# STM32-PROX_7.net
KiCad netlist of a schematic drawn in Altium Designer
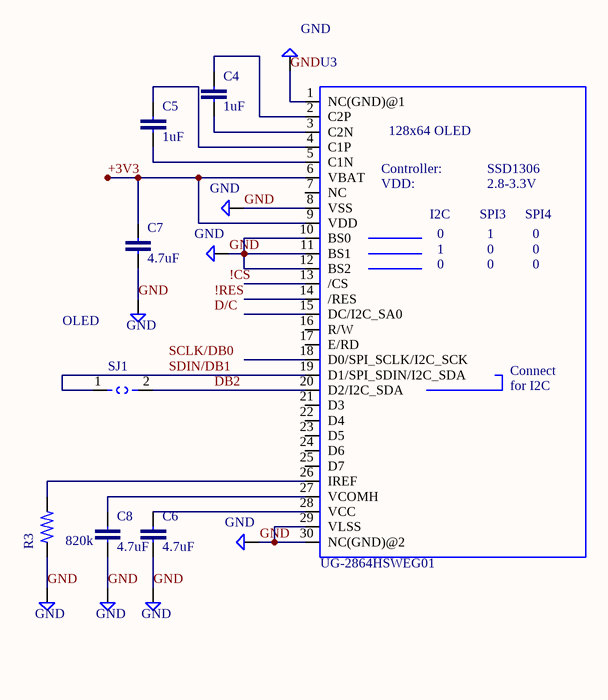
[diagram p0: STM32-PROX_7.SchDoc]

(export (version "E")
  (design (tool "Eeschema 10.0.6"))
  (components
    (comp (ref "C4") (value "1uF") (footprint "0805") (libsource (lib "STM32-PROX") (part "CAP0805")))
    (comp (ref "C5") (value "1uF") (footprint "0805") (libsource (lib "STM32-PROX") (part "CAP0805")))
    (comp (ref "C6") (value "4.7uF") (footprint "0805") (libsource (lib "STM32-PROX") (part "CAP0805")))
    (comp (ref "C7") (value "4.7uF") (footprint "0805") (libsource (lib "STM32-PROX") (part "CAP0805")))
    (comp (ref "C8") (value "4.7uF") (footprint "0805") (libsource (lib "STM32-PROX") (part "CAP0805")))
    (comp (ref "GND3") (value "GND") (libsource (lib "STM32-PROX") (part "GND")))
    (comp (ref "GND12") (value "GND") (libsource (lib "STM32-PROX") (part "GND")))
    (comp (ref "GND13") (value "GND") (libsource (lib "STM32-PROX") (part "GND")))
    (comp (ref "GND14") (value "GND") (libsource (lib "STM32-PROX") (part "GND")))
    (comp (ref "GND15") (value "GND") (libsource (lib "STM32-PROX") (part "GND")))
    (comp (ref "GND16") (value "GND") (libsource (lib "STM32-PROX") (part "GND")))
    (comp (ref "GND17") (value "GND") (libsource (lib "STM32-PROX") (part "GND")))
    (comp (ref "GND18") (value "GND") (libsource (lib "STM32-PROX") (part "GND")))
    (comp (ref "R3")
      (value "820k")
      (footprint "RLC_0603")
      (libsource (lib "STM32-PROX") (part "RESISTORRLC_0603"))
    )
    (comp (ref "SJ1")
      (value "~")
      (footprint "SOLDERJUMPER_REFLOW")
      (libsource (lib "STM32-PROX") (part "SOLDERJUMPERREFLOW"))
    )
    (comp (ref "U3")
      (value "UG-2864HSWEG01")
      (footprint "MICROBUILDER_UG-2864HSWEG01_0.96IN_WRAPAROUND")
      (libsource (lib "STM32-PROX") (part "MICROBUILDER_DISP_OLED_UG-2864HSWEG010.96{dblquote}"))
    )
  )
  (nets
    (net (code "3") (name "/+3V3") (class "Default")
      (node (ref "C7") (pin "1") (pinfunction "1_1") (pintype "passive"))
      (node (ref "U3") (pin "6") (pinfunction "VBAT_6") (pintype "passive"))
      (node (ref "U3") (pin "9") (pinfunction "VDD_9") (pintype "passive"))
    )
    (net (code "4") (name "/DB2") (class "Default")
      (node (ref "SJ1") (pin "2") (pinfunction "2_2") (pintype "passive"))
      (node (ref "U3") (pin "20") (pinfunction "D2/I2C_SDA_20") (pintype "passive"))
    )
    (net (code "6") (name "/GND") (class "Default")
      (node (ref "C6") (pin "2") (pinfunction "2_2") (pintype "passive"))
      (node (ref "C7") (pin "2") (pinfunction "2_2") (pintype "passive"))
      (node (ref "C8") (pin "2") (pinfunction "2_2") (pintype "passive"))
      (node (ref "GND12") (pin "0") (pinfunction "GND_0") (pintype "passive"))
      (node (ref "GND13") (pin "0") (pinfunction "GND_0") (pintype "passive"))
      (node (ref "GND14") (pin "0") (pinfunction "GND_0") (pintype "passive"))
      (node (ref "GND15") (pin "0") (pinfunction "GND_0") (pintype "passive"))
      (node (ref "GND16") (pin "0") (pinfunction "GND_0") (pintype "passive"))
      (node (ref "GND17") (pin "0") (pinfunction "GND_0") (pintype "passive"))
      (node (ref "GND18") (pin "0") (pinfunction "GND_0") (pintype "passive"))
      (node (ref "GND3") (pin "0") (pinfunction "GND_0") (pintype "passive"))
      (node (ref "R3") (pin "1") (pinfunction "1_1") (pintype "passive"))
      (node (ref "U3") (pin "1") (pinfunction "NC(GND)@1_1") (pintype "passive"))
      (node (ref "U3") (pin "10") (pinfunction "BS0_10") (pintype "passive"))
      (node (ref "U3") (pin "11") (pinfunction "BS1_11") (pintype "passive"))
      (node (ref "U3") (pin "12") (pinfunction "BS2_12") (pintype "passive"))
      (node (ref "U3") (pin "29") (pinfunction "VLSS_29") (pintype "passive"))
      (node (ref "U3") (pin "30") (pinfunction "NC(GND)@2_30") (pintype "passive"))
      (node (ref "U3") (pin "8") (pinfunction "VSS_8") (pintype "passive"))
    )
    (net (code "8") (name "/SDIN{slash}DB1") (class "Default")
      (node (ref "SJ1") (pin "1") (pinfunction "1_1") (pintype "passive"))
      (node (ref "U3") (pin "19") (pinfunction "D1/SPI_SDIN/I2C_SDA_19") (pintype "passive"))
    )
    (net (code "9") (name "Net-(U3-C1N)") (class "Default")
      (node (ref "C5") (pin "2") (pinfunction "2_2") (pintype "passive"))
      (node (ref "U3") (pin "5") (pinfunction "C1N_5") (pintype "passive"))
    )
    (net (code "10") (name "Net-(U3-C1P)") (class "Default")
      (node (ref "C5") (pin "1") (pinfunction "1_1") (pintype "passive"))
      (node (ref "U3") (pin "4") (pinfunction "C1P_4") (pintype "passive"))
    )
    (net (code "11") (name "Net-(U3-C2N)") (class "Default")
      (node (ref "C4") (pin "2") (pinfunction "2_2") (pintype "passive"))
      (node (ref "U3") (pin "3") (pinfunction "C2N_3") (pintype "passive"))
    )
    (net (code "12") (name "Net-(U3-C2P)") (class "Default")
      (node (ref "C4") (pin "1") (pinfunction "1_1") (pintype "passive"))
      (node (ref "U3") (pin "2") (pinfunction "C2P_2") (pintype "passive"))
    )
    (net (code "13") (name "Net-(U3-IREF)") (class "Default")
      (node (ref "R3") (pin "2") (pinfunction "2_2") (pintype "passive"))
      (node (ref "U3") (pin "26") (pinfunction "IREF_26") (pintype "passive"))
    )
    (net (code "14") (name "Net-(U3-VCC)") (class "Default")
      (node (ref "C6") (pin "1") (pinfunction "1_1") (pintype "passive"))
      (node (ref "U3") (pin "28") (pinfunction "VCC_28") (pintype "passive"))
    )
    (net (code "15") (name "Net-(U3-VCOMH)") (class "Default")
      (node (ref "C8") (pin "1") (pinfunction "1_1") (pintype "passive"))
      (node (ref "U3") (pin "27") (pinfunction "VCOMH_27") (pintype "passive"))
    )
    (net (code "16") (name "unconnected-(U3-D0{slash}SPI_SCLK{slash}I2C_SCK-Pad18)") (class "Default")
      (node (ref "U3") (pin "18") (pinfunction "D0/SPI_SCLK/I2C_SCK_18") (pintype "passive"))
    )
    (net (code "17") (name "unconnected-(U3-D3-Pad21)") (class "Default")
      (node (ref "U3") (pin "21") (pinfunction "D3_21") (pintype "passive"))
    )
    (net (code "18") (name "unconnected-(U3-D4-Pad22)") (class "Default")
      (node (ref "U3") (pin "22") (pinfunction "D4_22") (pintype "passive"))
    )
    (net (code "19") (name "unconnected-(U3-D5-Pad23)") (class "Default")
      (node (ref "U3") (pin "23") (pinfunction "D5_23") (pintype "passive"))
    )
    (net (code "20") (name "unconnected-(U3-D6-Pad24)") (class "Default")
      (node (ref "U3") (pin "24") (pinfunction "D6_24") (pintype "passive"))
    )
    (net (code "21") (name "unconnected-(U3-D7-Pad25)") (class "Default")
      (node (ref "U3") (pin "25") (pinfunction "D7_25") (pintype "passive"))
    )
    (net (code "22") (name "unconnected-(U3-DC{slash}I2C_SA0-Pad15)") (class "Default")
      (node (ref "U3") (pin "15") (pinfunction "DC/I2C_SA0_15") (pintype "passive"))
    )
    (net (code "23") (name "unconnected-(U3-E{slash}RD-Pad17)") (class "Default")
      (node (ref "U3") (pin "17") (pinfunction "E/RD_17") (pintype "passive"))
    )
    (net (code "24") (name "unconnected-(U3-NC-Pad7)") (class "Default")
      (node (ref "U3") (pin "7") (pinfunction "NC_7") (pintype "passive"))
    )
    (net (code "25") (name "unconnected-(U3-R{slash}W-Pad16)") (class "Default")
      (node (ref "U3") (pin "16") (pinfunction "R/W_16") (pintype "passive"))
    )
    (net (code "26") (name "unconnected-(U3-{slash}CS-Pad13)") (class "Default")
      (node (ref "U3") (pin "13") (pinfunction "/CS_13") (pintype "passive"))
    )
    (net (code "27") (name "unconnected-(U3-{slash}RES-Pad14)") (class "Default")
      (node (ref "U3") (pin "14") (pinfunction "/RES_14") (pintype "passive"))
    )
  )
)
